# guava1_1.net
KiCad netlist of a schematic drawn in EAGLE
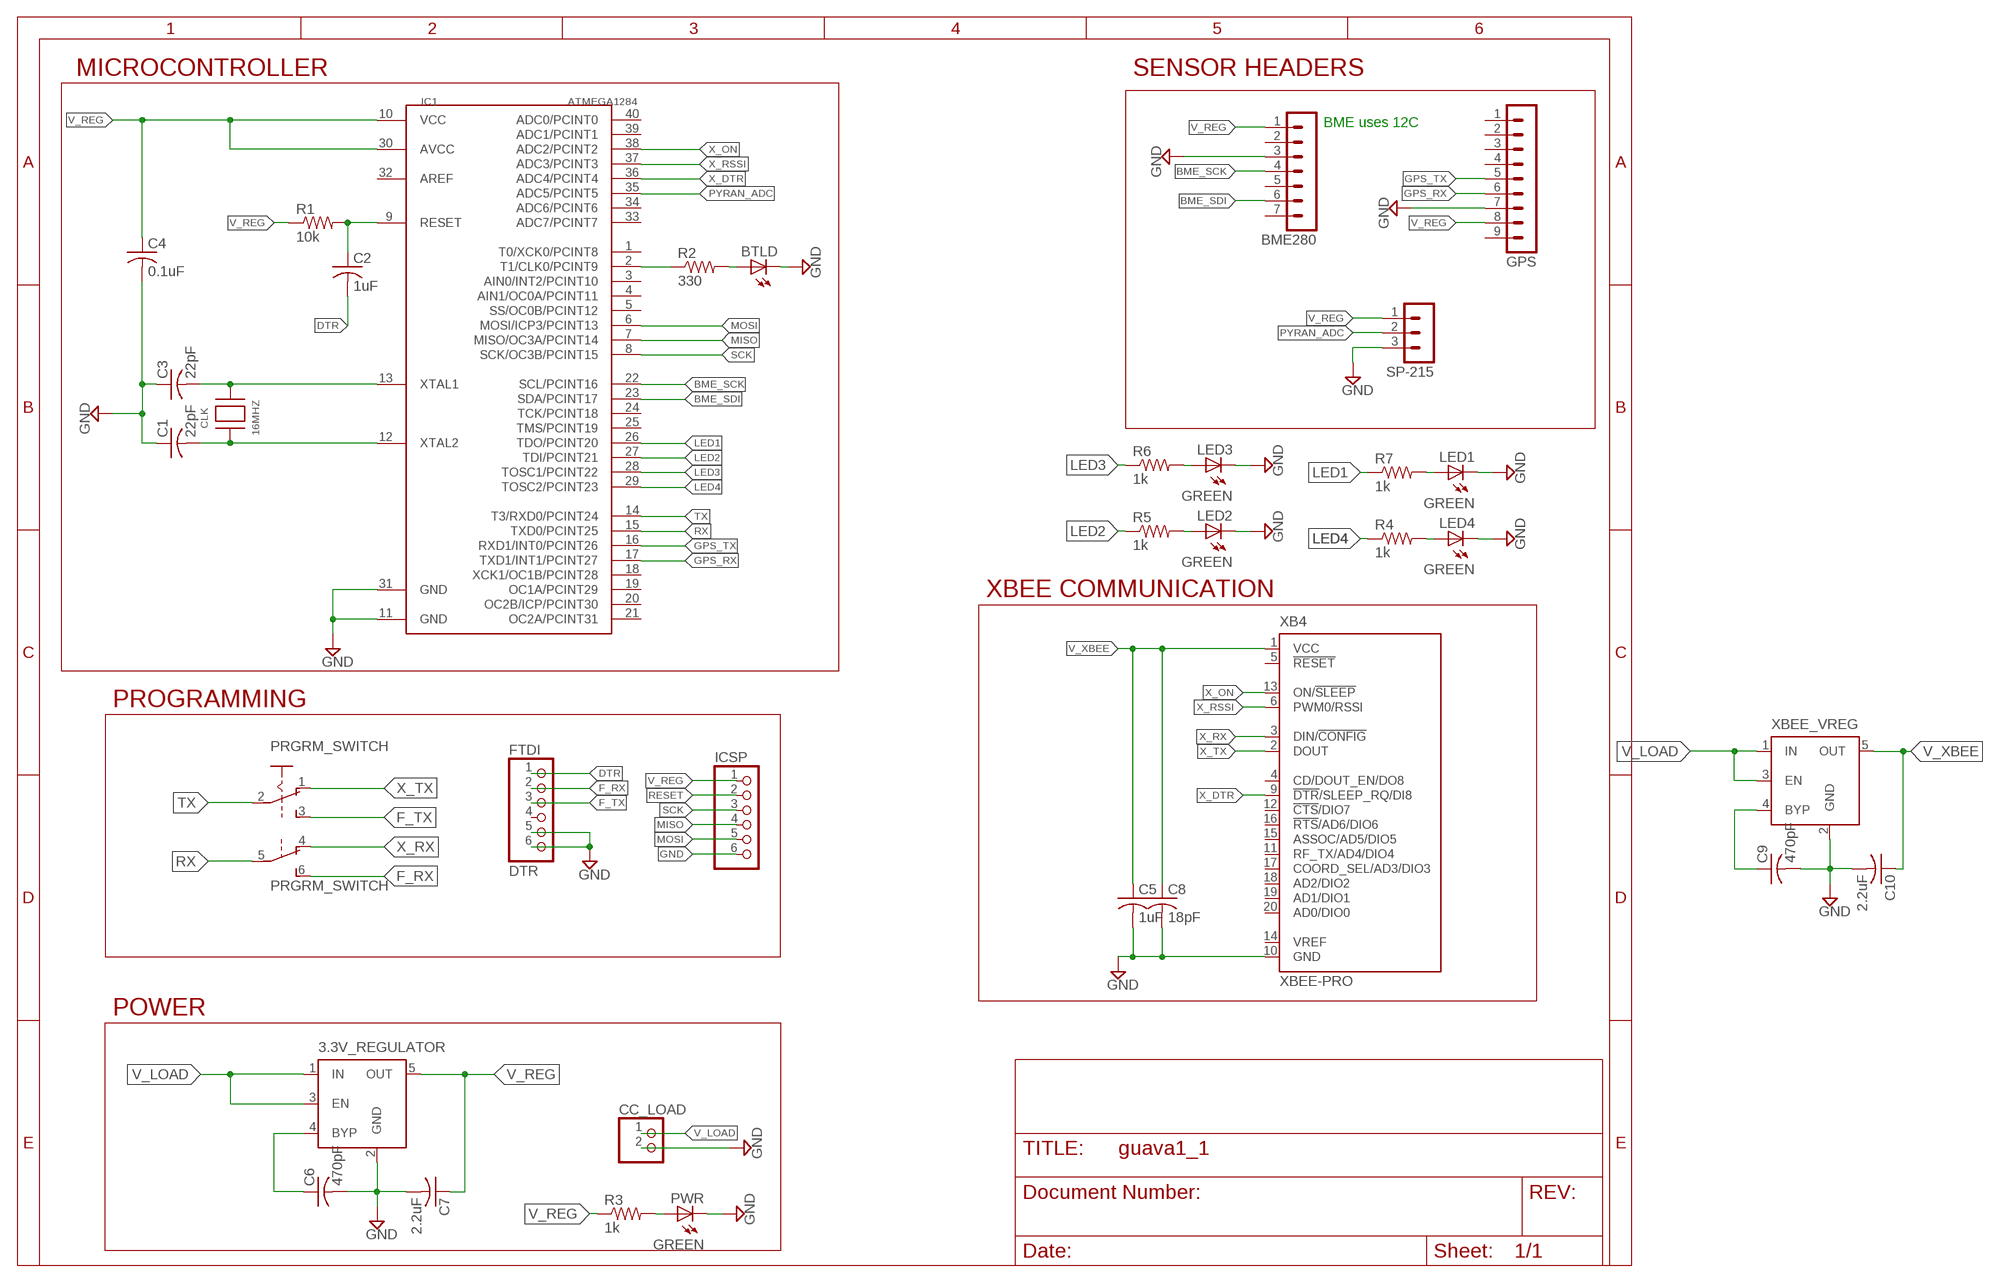
[diagram p0: schematic, sheet 1]

(export (version "E")
  (design (tool "Eeschema 10.0.6"))
  (components
    (comp (ref "3.3V_REGULATOR")
      (value "MIC5219XX")
      (footprint "eagle-import:SOT23-5")
      (libsource (lib "eagle-import") (part "MIC5219XX"))
    )
    (comp (ref "BME280")
      (value "MA07-1")
      (footprint "eagle-import:MA07-1")
      (libsource (lib "eagle-import") (part "MA07-1"))
    )
    (comp (ref "BTLD")
      (value "LEDCHIPLED_0805")
      (footprint "eagle-import:CHIPLED_0805")
      (libsource (lib "eagle-import") (part "LEDCHIPLED_0805"))
    )
    (comp (ref "C1")
      (value "22pF")
      (footprint "eagle-import:C0805")
      (libsource (lib "eagle-import") (part "C-USC0805"))
    )
    (comp (ref "C2")
      (value "1uF")
      (footprint "eagle-import:C0805")
      (libsource (lib "eagle-import") (part "C-USC0805"))
    )
    (comp (ref "C3")
      (value "22pF")
      (footprint "eagle-import:C0805")
      (libsource (lib "eagle-import") (part "C-USC0805"))
    )
    (comp (ref "C4")
      (value "0.1uF")
      (footprint "eagle-import:C0805")
      (libsource (lib "eagle-import") (part "C-USC0805"))
    )
    (comp (ref "C5")
      (value "1uF")
      (footprint "eagle-import:C0805")
      (libsource (lib "eagle-import") (part "C-USC0805"))
    )
    (comp (ref "C6")
      (value "470pF")
      (footprint "eagle-import:C0805")
      (libsource (lib "eagle-import") (part "C-USC0805"))
    )
    (comp (ref "C7")
      (value "2.2uF")
      (footprint "eagle-import:C0805")
      (libsource (lib "eagle-import") (part "C-USC0805"))
    )
    (comp (ref "C8")
      (value "18pF")
      (footprint "eagle-import:C0805")
      (libsource (lib "eagle-import") (part "C-USC0805"))
    )
    (comp (ref "C9")
      (value "470pF")
      (footprint "eagle-import:C0805")
      (libsource (lib "eagle-import") (part "C-USC0805"))
    )
    (comp (ref "C10")
      (value "2.2uF")
      (footprint "eagle-import:C0805")
      (libsource (lib "eagle-import") (part "C-USC0805"))
    )
    (comp (ref "CC_LOAD")
      (value "PINHD-1X2")
      (footprint "eagle-import:1X02")
      (libsource (lib "eagle-import") (part "PINHD-1X2"))
    )
    (comp (ref "CLK")
      (value "16MHZ")
      (footprint "eagle-import:NX8045")
      (libsource (lib "eagle-import") (part "XTALNX8045"))
    )
    (comp (ref "FTDI")
      (value "DTR")
      (footprint "eagle-import:1X06")
      (libsource (lib "eagle-import") (part "PINHD-1X6"))
    )
    (comp (ref "GPS")
      (value "MA09-1")
      (footprint "eagle-import:MA09-1")
      (libsource (lib "eagle-import") (part "MA09-1"))
    )
    (comp (ref "IC1")
      (value "ATMEGA1284")
      (footprint "eagle-import:DIL40")
      (libsource (lib "eagle-import") (part "MEGA1284P"))
    )
    (comp (ref "ICSP")
      (value "PINHD-1X6")
      (footprint "eagle-import:1X06")
      (libsource (lib "eagle-import") (part "pinhead_PINHD-1X6"))
    )
    (comp (ref "LED1")
      (value "GREEN")
      (footprint "eagle-import:CHIPLED_0805")
      (libsource (lib "eagle-import") (part "LEDCHIPLED_0805"))
    )
    (comp (ref "LED2")
      (value "GREEN")
      (footprint "eagle-import:CHIPLED_0805")
      (libsource (lib "eagle-import") (part "LEDCHIPLED_0805"))
    )
    (comp (ref "LED3")
      (value "GREEN")
      (footprint "eagle-import:CHIPLED_0805")
      (libsource (lib "eagle-import") (part "LEDCHIPLED_0805"))
    )
    (comp (ref "LED4")
      (value "GREEN")
      (footprint "eagle-import:CHIPLED_0805")
      (libsource (lib "eagle-import") (part "LEDCHIPLED_0805"))
    )
    (comp (ref "PRGRM_SWITCH")
      (value "A68-A31")
      (footprint "eagle-import:A68-A31")
      (libsource (lib "eagle-import") (part "A68-A31"))
    )
    (comp (ref "PWR")
      (value "GREEN")
      (footprint "eagle-import:CHIPLED_0805")
      (libsource (lib "eagle-import") (part "LEDCHIPLED_0805"))
    )
    (comp (ref "R1")
      (value "10k")
      (footprint "eagle-import:R0805")
      (libsource (lib "eagle-import") (part "R-US_R0805"))
    )
    (comp (ref "R2")
      (value "330")
      (footprint "eagle-import:R0805")
      (libsource (lib "eagle-import") (part "R-US_R0805"))
    )
    (comp (ref "R3")
      (value "1k")
      (footprint "eagle-import:R0805")
      (libsource (lib "eagle-import") (part "R-US_R0805"))
    )
    (comp (ref "R4")
      (value "1k")
      (footprint "eagle-import:R0805")
      (libsource (lib "eagle-import") (part "R-US_R0805"))
    )
    (comp (ref "R5")
      (value "1k")
      (footprint "eagle-import:R0805")
      (libsource (lib "eagle-import") (part "R-US_R0805"))
    )
    (comp (ref "R6")
      (value "1k")
      (footprint "eagle-import:R0805")
      (libsource (lib "eagle-import") (part "R-US_R0805"))
    )
    (comp (ref "R7")
      (value "1k")
      (footprint "eagle-import:R0805")
      (libsource (lib "eagle-import") (part "R-US_R0805"))
    )
    (comp (ref "SP-215")
      (value "MA03-1")
      (footprint "eagle-import:MA03-1")
      (libsource (lib "eagle-import") (part "MA03-1"))
    )
    (comp (ref "XB4")
      (value "XBEE-PRO")
      (footprint "eagle-import:XBEE-PRO")
      (fields (field (name "MPN") "XBP24-AWI-001"))
      (libsource (lib "eagle-import") (part "XBEE-PRO"))
    )
    (comp (ref "XBEE_VREG")
      (value "MIC5219XX")
      (footprint "eagle-import:SOT23-5")
      (libsource (lib "eagle-import") (part "MIC5219XX"))
    )
  )
  (nets
    (net (code "1") (name "BME_SCK") (class "Default")
      (node (ref "BME280") (pin "4") (pinfunction "4_4") (pintype "passive"))
      (node (ref "IC1") (pin "22") (pinfunction "SCL/PCINT16_22") (pintype "bidirectional"))
    )
    (net (code "2") (name "BME_SDI") (class "Default")
      (node (ref "BME280") (pin "6") (pinfunction "6_6") (pintype "passive"))
      (node (ref "IC1") (pin "23") (pinfunction "SDA/PCINT17_23") (pintype "bidirectional"))
    )
    (net (code "3") (name "DTR") (class "Default")
      (node (ref "C2") (pin "2") (pinfunction "2_2") (pintype "passive"))
      (node (ref "FTDI") (pin "1") (pinfunction "1_1") (pintype "passive"))
    )
    (net (code "4") (name "F_RX") (class "Default")
      (node (ref "FTDI") (pin "2") (pinfunction "2_2") (pintype "passive"))
      (node (ref "PRGRM_SWITCH") (pin "6") (pinfunction "S_6") (pintype "passive"))
    )
    (net (code "5") (name "F_TX") (class "Default")
      (node (ref "FTDI") (pin "3") (pinfunction "3_3") (pintype "passive"))
      (node (ref "PRGRM_SWITCH") (pin "3") (pinfunction "S_3") (pintype "passive"))
    )
    (net (code "6") (name "GND") (class "Default")
      (node (ref "3.3V_REGULATOR") (pin "2") (pinfunction "GND_2") (pintype "power_in"))
      (node (ref "BME280") (pin "3") (pinfunction "3_3") (pintype "passive"))
      (node (ref "BTLD") (pin "C") (pinfunction "C_C") (pintype "passive"))
      (node (ref "C1") (pin "1") (pinfunction "1_1") (pintype "passive"))
      (node (ref "C10") (pin "2") (pinfunction "2_2") (pintype "passive"))
      (node (ref "C3") (pin "1") (pinfunction "1_1") (pintype "passive"))
      (node (ref "C4") (pin "2") (pinfunction "2_2") (pintype "passive"))
      (node (ref "C5") (pin "2") (pinfunction "2_2") (pintype "passive"))
      (node (ref "C6") (pin "2") (pinfunction "2_2") (pintype "passive"))
      (node (ref "C7") (pin "2") (pinfunction "2_2") (pintype "passive"))
      (node (ref "C8") (pin "2") (pinfunction "2_2") (pintype "passive"))
      (node (ref "C9") (pin "2") (pinfunction "2_2") (pintype "passive"))
      (node (ref "CC_LOAD") (pin "2") (pinfunction "2_2") (pintype "passive"))
      (node (ref "FTDI") (pin "5") (pinfunction "5_5") (pintype "passive"))
      (node (ref "FTDI") (pin "6") (pinfunction "6_6") (pintype "passive"))
      (node (ref "GPS") (pin "7") (pinfunction "7_7") (pintype "passive"))
      (node (ref "IC1") (pin "11") (pinfunction "GND_11") (pintype "bidirectional"))
      (node (ref "IC1") (pin "31") (pinfunction "GND_31") (pintype "bidirectional"))
      (node (ref "ICSP") (pin "6") (pinfunction "6_6") (pintype "passive"))
      (node (ref "LED1") (pin "C") (pinfunction "C_C") (pintype "passive"))
      (node (ref "LED2") (pin "C") (pinfunction "C_C") (pintype "passive"))
      (node (ref "LED3") (pin "C") (pinfunction "C_C") (pintype "passive"))
      (node (ref "LED4") (pin "C") (pinfunction "C_C") (pintype "passive"))
      (node (ref "PWR") (pin "C") (pinfunction "C_C") (pintype "passive"))
      (node (ref "SP-215") (pin "3") (pinfunction "3_3") (pintype "passive"))
      (node (ref "XB4") (pin "10") (pinfunction "GND_10") (pintype "power_in"))
      (node (ref "XBEE_VREG") (pin "2") (pinfunction "GND_2") (pintype "power_in"))
    )
    (net (code "7") (name "GPS_RX") (class "Default")
      (node (ref "GPS") (pin "6") (pinfunction "6_6") (pintype "passive"))
      (node (ref "IC1") (pin "17") (pinfunction "TXD1/INT1/PCINT27_17") (pintype "bidirectional"))
    )
    (net (code "8") (name "GPS_TX") (class "Default")
      (node (ref "GPS") (pin "5") (pinfunction "5_5") (pintype "passive"))
      (node (ref "IC1") (pin "16") (pinfunction "RXD1/INT0/PCINT26_16") (pintype "bidirectional"))
    )
    (net (code "9") (name "LED1") (class "Default")
      (node (ref "IC1") (pin "26") (pinfunction "TDO/PCINT20_26") (pintype "bidirectional"))
      (node (ref "R7") (pin "1") (pinfunction "1_1") (pintype "passive"))
    )
    (net (code "10") (name "LED2") (class "Default")
      (node (ref "IC1") (pin "27") (pinfunction "TDI/PCINT21_27") (pintype "bidirectional"))
      (node (ref "R5") (pin "1") (pinfunction "1_1") (pintype "passive"))
    )
    (net (code "11") (name "LED3") (class "Default")
      (node (ref "IC1") (pin "28") (pinfunction "TOSC1/PCINT22_28") (pintype "bidirectional"))
      (node (ref "R6") (pin "1") (pinfunction "1_1") (pintype "passive"))
    )
    (net (code "12") (name "LED4") (class "Default")
      (node (ref "IC1") (pin "29") (pinfunction "TOSC2/PCINT23_29") (pintype "bidirectional"))
      (node (ref "R4") (pin "1") (pinfunction "1_1") (pintype "passive"))
    )
    (net (code "13") (name "MISO") (class "Default")
      (node (ref "IC1") (pin "7") (pinfunction "MISO/OC3A/PCINT14_7") (pintype "bidirectional"))
      (node (ref "ICSP") (pin "4") (pinfunction "4_4") (pintype "passive"))
    )
    (net (code "14") (name "MOSI") (class "Default")
      (node (ref "IC1") (pin "6") (pinfunction "MOSI/ICP3/PCINT13_6") (pintype "bidirectional"))
      (node (ref "ICSP") (pin "5") (pinfunction "5_5") (pintype "passive"))
    )
    (net (code "15") (name "Net-(3.3V_REGULATOR-BYP)") (class "Default")
      (node (ref "3.3V_REGULATOR") (pin "4") (pinfunction "BYP_4") (pintype "passive"))
      (node (ref "C6") (pin "1") (pinfunction "1_1") (pintype "passive"))
    )
    (net (code "16") (name "Net-(BTLD-PadA)") (class "Default")
      (node (ref "BTLD") (pin "A") (pinfunction "A_A") (pintype "passive"))
      (node (ref "R2") (pin "2") (pinfunction "2_2") (pintype "passive"))
    )
    (net (code "17") (name "Net-(IC1-RESET)") (class "Default")
      (node (ref "C2") (pin "1") (pinfunction "1_1") (pintype "passive"))
      (node (ref "IC1") (pin "9") (pinfunction "RESET_9") (pintype "bidirectional"))
      (node (ref "R1") (pin "2") (pinfunction "2_2") (pintype "passive"))
    )
    (net (code "18") (name "Net-(IC1-T1{slash}CLK0{slash}PCINT9)") (class "Default")
      (node (ref "IC1") (pin "2") (pinfunction "T1/CLK0/PCINT9_2") (pintype "bidirectional"))
      (node (ref "R2") (pin "1") (pinfunction "1_1") (pintype "passive"))
    )
    (net (code "19") (name "Net-(IC1-XTAL1)") (class "Default")
      (node (ref "C3") (pin "2") (pinfunction "2_2") (pintype "passive"))
      (node (ref "CLK") (pin "P$2") (pinfunction "P$2_P$2") (pintype "bidirectional"))
      (node (ref "IC1") (pin "13") (pinfunction "XTAL1_13") (pintype "bidirectional"))
    )
    (net (code "20") (name "Net-(IC1-XTAL2)") (class "Default")
      (node (ref "C1") (pin "2") (pinfunction "2_2") (pintype "passive"))
      (node (ref "CLK") (pin "P$1") (pinfunction "P$1_P$1") (pintype "bidirectional"))
      (node (ref "IC1") (pin "12") (pinfunction "XTAL2_12") (pintype "bidirectional"))
    )
    (net (code "21") (name "Net-(LED1-PadA)") (class "Default")
      (node (ref "LED1") (pin "A") (pinfunction "A_A") (pintype "passive"))
      (node (ref "R7") (pin "2") (pinfunction "2_2") (pintype "passive"))
    )
    (net (code "22") (name "Net-(LED2-PadA)") (class "Default")
      (node (ref "LED2") (pin "A") (pinfunction "A_A") (pintype "passive"))
      (node (ref "R5") (pin "2") (pinfunction "2_2") (pintype "passive"))
    )
    (net (code "23") (name "Net-(LED3-PadA)") (class "Default")
      (node (ref "LED3") (pin "A") (pinfunction "A_A") (pintype "passive"))
      (node (ref "R6") (pin "2") (pinfunction "2_2") (pintype "passive"))
    )
    (net (code "24") (name "Net-(LED4-PadA)") (class "Default")
      (node (ref "LED4") (pin "A") (pinfunction "A_A") (pintype "passive"))
      (node (ref "R4") (pin "2") (pinfunction "2_2") (pintype "passive"))
    )
    (net (code "25") (name "Net-(PWR-PadA)") (class "Default")
      (node (ref "PWR") (pin "A") (pinfunction "A_A") (pintype "passive"))
      (node (ref "R3") (pin "2") (pinfunction "2_2") (pintype "passive"))
    )
    (net (code "26") (name "Net-(XBEE_VREG-BYP)") (class "Default")
      (node (ref "C9") (pin "1") (pinfunction "1_1") (pintype "passive"))
      (node (ref "XBEE_VREG") (pin "4") (pinfunction "BYP_4") (pintype "passive"))
    )
    (net (code "27") (name "PYRAN_ADC") (class "Default")
      (node (ref "IC1") (pin "35") (pinfunction "ADC5/PCINT5_35") (pintype "bidirectional"))
      (node (ref "SP-215") (pin "2") (pinfunction "2_2") (pintype "passive"))
    )
    (net (code "28") (name "RESET") (class "Default")
      (node (ref "ICSP") (pin "2") (pinfunction "2_2") (pintype "passive"))
    )
    (net (code "29") (name "RX") (class "Default")
      (node (ref "IC1") (pin "15") (pinfunction "TXD0/PCINT25_15") (pintype "bidirectional"))
      (node (ref "PRGRM_SWITCH") (pin "5") (pinfunction "P_5") (pintype "passive"))
    )
    (net (code "30") (name "SCK") (class "Default")
      (node (ref "IC1") (pin "8") (pinfunction "SCK/OC3B/PCINT15_8") (pintype "bidirectional"))
      (node (ref "ICSP") (pin "3") (pinfunction "3_3") (pintype "passive"))
    )
    (net (code "31") (name "TX") (class "Default")
      (node (ref "IC1") (pin "14") (pinfunction "T3/RXD0/PCINT24_14") (pintype "bidirectional"))
      (node (ref "PRGRM_SWITCH") (pin "2") (pinfunction "P_2") (pintype "passive"))
    )
    (net (code "32") (name "V_LOAD") (class "Default")
      (node (ref "3.3V_REGULATOR") (pin "1") (pinfunction "IN_1") (pintype "input"))
      (node (ref "3.3V_REGULATOR") (pin "3") (pinfunction "EN_3") (pintype "input"))
      (node (ref "CC_LOAD") (pin "1") (pinfunction "1_1") (pintype "passive"))
      (node (ref "XBEE_VREG") (pin "1") (pinfunction "IN_1") (pintype "input"))
      (node (ref "XBEE_VREG") (pin "3") (pinfunction "EN_3") (pintype "input"))
    )
    (net (code "33") (name "V_REG") (class "Default")
      (node (ref "3.3V_REGULATOR") (pin "5") (pinfunction "OUT_5") (pintype "output"))
      (node (ref "BME280") (pin "1") (pinfunction "1_1") (pintype "passive"))
      (node (ref "C4") (pin "1") (pinfunction "1_1") (pintype "passive"))
      (node (ref "C7") (pin "1") (pinfunction "1_1") (pintype "passive"))
      (node (ref "GPS") (pin "8") (pinfunction "8_8") (pintype "passive"))
      (node (ref "IC1") (pin "10") (pinfunction "VCC_10") (pintype "bidirectional"))
      (node (ref "IC1") (pin "30") (pinfunction "AVCC_30") (pintype "bidirectional"))
      (node (ref "ICSP") (pin "1") (pinfunction "1_1") (pintype "passive"))
      (node (ref "R1") (pin "1") (pinfunction "1_1") (pintype "passive"))
      (node (ref "R3") (pin "1") (pinfunction "1_1") (pintype "passive"))
      (node (ref "SP-215") (pin "1") (pinfunction "1_1") (pintype "passive"))
    )
    (net (code "34") (name "V_XBEE") (class "Default")
      (node (ref "C10") (pin "1") (pinfunction "1_1") (pintype "passive"))
      (node (ref "C5") (pin "1") (pinfunction "1_1") (pintype "passive"))
      (node (ref "C8") (pin "1") (pinfunction "1_1") (pintype "passive"))
      (node (ref "XB4") (pin "1") (pinfunction "VCC_1") (pintype "power_in"))
      (node (ref "XBEE_VREG") (pin "5") (pinfunction "OUT_5") (pintype "output"))
    )
    (net (code "35") (name "X_DTR") (class "Default")
      (node (ref "IC1") (pin "36") (pinfunction "ADC4/PCINT4_36") (pintype "bidirectional"))
      (node (ref "XB4") (pin "9") (pinfunction "~{DTR}/SLEEP_RQ/DI8_9") (pintype "bidirectional"))
    )
    (net (code "36") (name "X_ON") (class "Default")
      (node (ref "IC1") (pin "38") (pinfunction "ADC2/PCINT2_38") (pintype "bidirectional"))
      (node (ref "XB4") (pin "13") (pinfunction "ON/~{SLEEP}_13") (pintype "output"))
    )
    (net (code "37") (name "X_RSSI") (class "Default")
      (node (ref "IC1") (pin "37") (pinfunction "ADC3/PCINT3_37") (pintype "bidirectional"))
      (node (ref "XB4") (pin "6") (pinfunction "PWM0/RSSI_6") (pintype "output"))
    )
    (net (code "38") (name "X_RX") (class "Default")
      (node (ref "PRGRM_SWITCH") (pin "4") (pinfunction "O_4") (pintype "passive"))
      (node (ref "XB4") (pin "3") (pinfunction "DIN/~{CONFIG}_3") (pintype "input"))
    )
    (net (code "39") (name "X_TX") (class "Default")
      (node (ref "PRGRM_SWITCH") (pin "1") (pinfunction "O_1") (pintype "passive"))
      (node (ref "XB4") (pin "2") (pinfunction "DOUT_2") (pintype "output"))
    )
    (net (code "40") (name "unconnected-(BME280-Pad2)") (class "Default")
      (node (ref "BME280") (pin "2") (pinfunction "2_2") (pintype "passive"))
    )
    (net (code "41") (name "unconnected-(BME280-Pad5)") (class "Default")
      (node (ref "BME280") (pin "5") (pinfunction "5_5") (pintype "passive"))
    )
    (net (code "42") (name "unconnected-(BME280-Pad7)") (class "Default")
      (node (ref "BME280") (pin "7") (pinfunction "7_7") (pintype "passive"))
    )
    (net (code "43") (name "unconnected-(FTDI-Pad4)") (class "Default")
      (node (ref "FTDI") (pin "4") (pinfunction "4_4") (pintype "passive"))
    )
    (net (code "44") (name "unconnected-(GPS-Pad1)") (class "Default")
      (node (ref "GPS") (pin "1") (pinfunction "1_1") (pintype "passive"))
    )
    (net (code "45") (name "unconnected-(GPS-Pad2)") (class "Default")
      (node (ref "GPS") (pin "2") (pinfunction "2_2") (pintype "passive"))
    )
    (net (code "46") (name "unconnected-(GPS-Pad3)") (class "Default")
      (node (ref "GPS") (pin "3") (pinfunction "3_3") (pintype "passive"))
    )
    (net (code "47") (name "unconnected-(GPS-Pad4)") (class "Default")
      (node (ref "GPS") (pin "4") (pinfunction "4_4") (pintype "passive"))
    )
    (net (code "48") (name "unconnected-(GPS-Pad9)") (class "Default")
      (node (ref "GPS") (pin "9") (pinfunction "9_9") (pintype "passive"))
    )
    (net (code "49") (name "unconnected-(IC1-ADC0{slash}PCINT0-Pad40)") (class "Default")
      (node (ref "IC1") (pin "40") (pinfunction "ADC0/PCINT0_40") (pintype "bidirectional"))
    )
    (net (code "50") (name "unconnected-(IC1-ADC1{slash}PCINT1-Pad39)") (class "Default")
      (node (ref "IC1") (pin "39") (pinfunction "ADC1/PCINT1_39") (pintype "bidirectional"))
    )
    (net (code "51") (name "unconnected-(IC1-ADC6{slash}PCINT6-Pad34)") (class "Default")
      (node (ref "IC1") (pin "34") (pinfunction "ADC6/PCINT6_34") (pintype "bidirectional"))
    )
    (net (code "52") (name "unconnected-(IC1-ADC7{slash}PCINT7-Pad33)") (class "Default")
      (node (ref "IC1") (pin "33") (pinfunction "ADC7/PCINT7_33") (pintype "bidirectional"))
    )
    (net (code "53") (name "unconnected-(IC1-AIN0{slash}INT2{slash}PCINT10-Pad3)") (class "Default")
      (node (ref "IC1") (pin "3") (pinfunction "AIN0/INT2/PCINT10_3") (pintype "bidirectional"))
    )
    (net (code "54") (name "unconnected-(IC1-AIN1{slash}OC0A{slash}PCINT11-Pad4)") (class "Default")
      (node (ref "IC1") (pin "4") (pinfunction "AIN1/OC0A/PCINT11_4") (pintype "bidirectional"))
    )
    (net (code "55") (name "unconnected-(IC1-AREF-Pad32)") (class "Default")
      (node (ref "IC1") (pin "32") (pinfunction "AREF_32") (pintype "bidirectional"))
    )
    (net (code "56") (name "unconnected-(IC1-OC1A{slash}PCINT29-Pad19)") (class "Default")
      (node (ref "IC1") (pin "19") (pinfunction "OC1A/PCINT29_19") (pintype "bidirectional"))
    )
    (net (code "57") (name "unconnected-(IC1-OC2A{slash}PCINT31-Pad21)") (class "Default")
      (node (ref "IC1") (pin "21") (pinfunction "OC2A/PCINT31_21") (pintype "bidirectional"))
    )
    (net (code "58") (name "unconnected-(IC1-OC2B{slash}ICP{slash}PCINT30-Pad20)") (class "Default")
      (node (ref "IC1") (pin "20") (pinfunction "OC2B/ICP/PCINT30_20") (pintype "bidirectional"))
    )
    (net (code "59") (name "unconnected-(IC1-SS{slash}OC0B{slash}PCINT12-Pad5)") (class "Default")
      (node (ref "IC1") (pin "5") (pinfunction "SS/OC0B/PCINT12_5") (pintype "bidirectional"))
    )
    (net (code "60") (name "unconnected-(IC1-T0{slash}XCK0{slash}PCINT8-Pad1)") (class "Default")
      (node (ref "IC1") (pin "1") (pinfunction "T0/XCK0/PCINT8_1") (pintype "bidirectional"))
    )
    (net (code "61") (name "unconnected-(IC1-TCK{slash}PCINT18-Pad24)") (class "Default")
      (node (ref "IC1") (pin "24") (pinfunction "TCK/PCINT18_24") (pintype "bidirectional"))
    )
    (net (code "62") (name "unconnected-(IC1-TMS{slash}PCINT19-Pad25)") (class "Default")
      (node (ref "IC1") (pin "25") (pinfunction "TMS/PCINT19_25") (pintype "bidirectional"))
    )
    (net (code "63") (name "unconnected-(IC1-XCK1{slash}OC1B{slash}PCINT28-Pad18)") (class "Default")
      (node (ref "IC1") (pin "18") (pinfunction "XCK1/OC1B/PCINT28_18") (pintype "bidirectional"))
    )
    (net (code "64") (name "unconnected-(XB4-AD0{slash}DIO0-Pad20)") (class "Default")
      (node (ref "XB4") (pin "20") (pinfunction "AD0/DIO0_20") (pintype "bidirectional"))
    )
    (net (code "65") (name "unconnected-(XB4-AD1{slash}DIO1-Pad19)") (class "Default")
      (node (ref "XB4") (pin "19") (pinfunction "AD1/DIO1_19") (pintype "bidirectional"))
    )
    (net (code "66") (name "unconnected-(XB4-AD2{slash}DIO2-Pad18)") (class "Default")
      (node (ref "XB4") (pin "18") (pinfunction "AD2/DIO2_18") (pintype "bidirectional"))
    )
    (net (code "67") (name "unconnected-(XB4-ASSOC{slash}AD5{slash}DIO5-Pad15)") (class "Default")
      (node (ref "XB4") (pin "15") (pinfunction "ASSOC/AD5/DIO5_15") (pintype "bidirectional"))
    )
    (net (code "68") (name "unconnected-(XB4-CD{slash}DOUT_EN{slash}DO8-Pad4)") (class "Default")
      (node (ref "XB4") (pin "4") (pinfunction "CD/DOUT_EN/DO8_4") (pintype "output"))
    )
    (net (code "69") (name "unconnected-(XB4-COORD_SEL{slash}AD3{slash}DIO3-Pad17)") (class "Default")
      (node (ref "XB4") (pin "17") (pinfunction "COORD_SEL/AD3/DIO3_17") (pintype "bidirectional"))
    )
    (net (code "70") (name "unconnected-(XB4-RF_TX{slash}AD4{slash}DIO4-Pad11)") (class "Default")
      (node (ref "XB4") (pin "11") (pinfunction "RF_TX/AD4/DIO4_11") (pintype "bidirectional"))
    )
    (net (code "71") (name "unconnected-(XB4-VREF-Pad14)") (class "Default")
      (node (ref "XB4") (pin "14") (pinfunction "VREF_14") (pintype "input"))
    )
    (net (code "72") (name "unconnected-(XB4-~{CTS}{slash}DIO7-Pad12)") (class "Default")
      (node (ref "XB4") (pin "12") (pinfunction "~{CTS}/DIO7_12") (pintype "bidirectional"))
    )
    (net (code "73") (name "unconnected-(XB4-~{RESET}-Pad5)") (class "Default")
      (node (ref "XB4") (pin "5") (pinfunction "~{RESET}_5") (pintype "input"))
    )
    (net (code "74") (name "unconnected-(XB4-~{RTS}{slash}AD6{slash}DIO6-Pad16)") (class "Default")
      (node (ref "XB4") (pin "16") (pinfunction "~{RTS}/AD6/DIO6_16") (pintype "bidirectional"))
    )
  )
)
